# DebugSwitch.net
KiCad netlist of a schematic drawn in Altium Designer
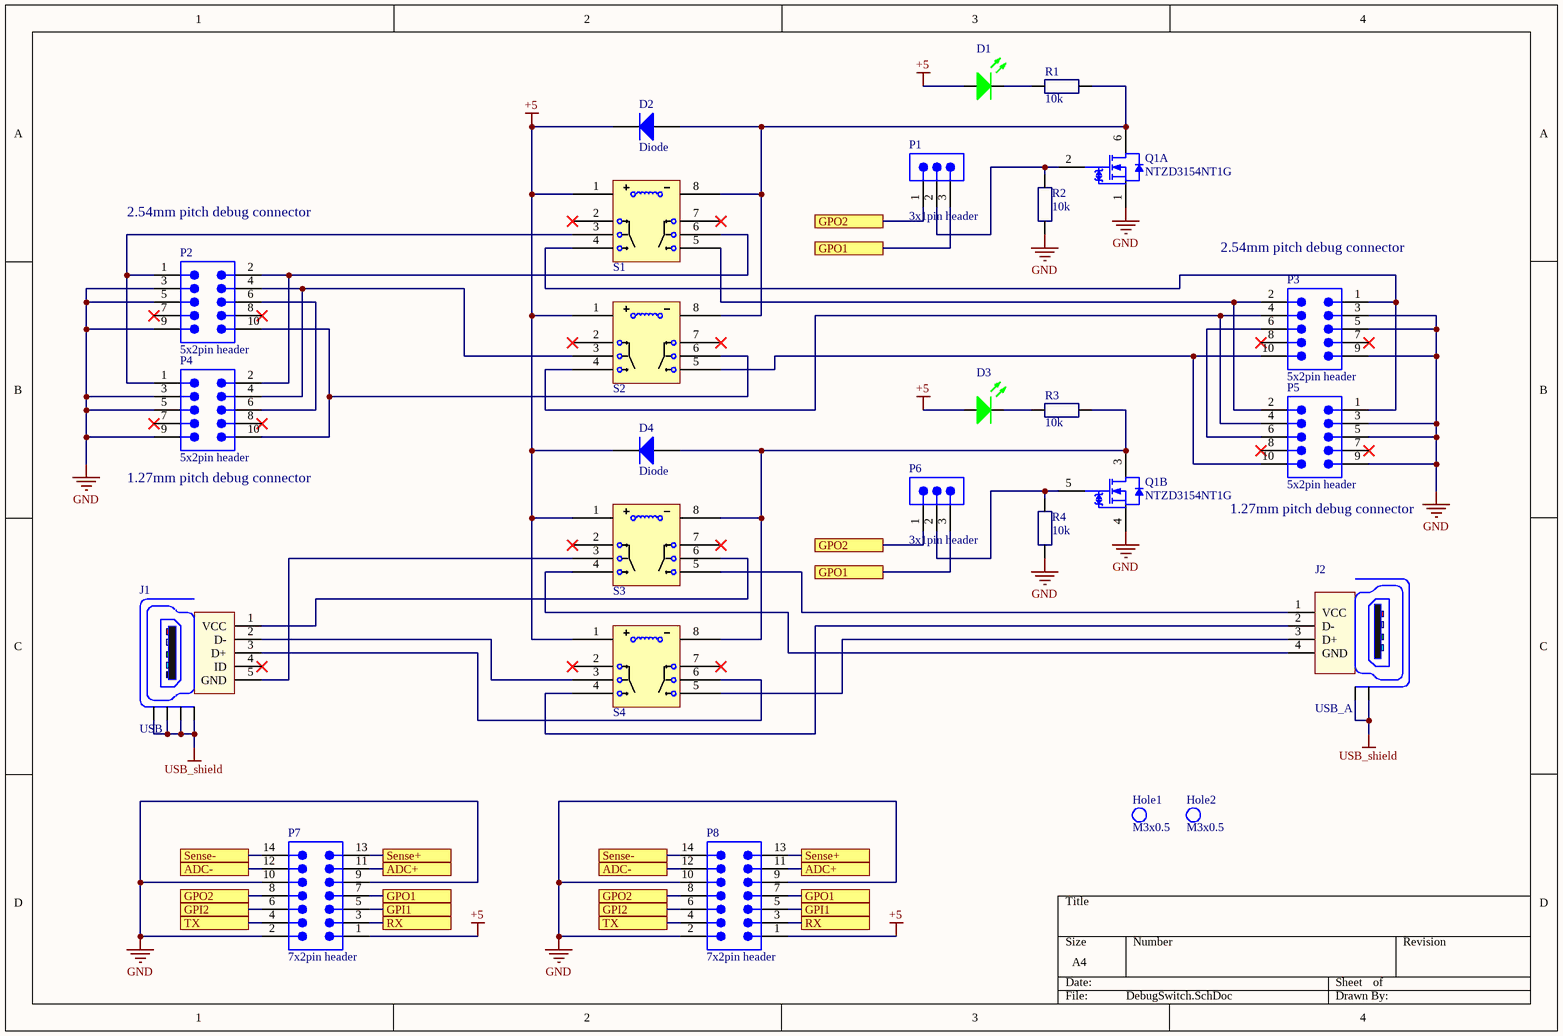
[diagram p0: DebugSwitch.SchDoc]

(export (version "E")
  (design (tool "Eeschema 10.0.6"))
  (components
    (comp (ref "D1")
      (value "LED_GREEN")
      (footprint "LED_0603")
      (libsource (lib "Bjorn_temp") (part "LED_GREEN"))
    )
    (comp (ref "D2")
      (value "Diode")
      (footprint "SOD-123")
      (description "Generic diode")
      (libsource (lib "Bjorn_temp") (part "Diode"))
    )
    (comp (ref "D3")
      (value "LED_GREEN")
      (footprint "LED_0603")
      (libsource (lib "Bjorn_temp") (part "LED_GREEN"))
    )
    (comp (ref "D4")
      (value "Diode")
      (footprint "SOD-123")
      (description "Generic diode")
      (libsource (lib "Bjorn_temp") (part "Diode"))
    )
    (comp (ref "Hole1") (value "M3x0.5") (footprint "M3x0.5") (libsource (lib "Bjorn_temp") (part "M3x0.5")))
    (comp (ref "Hole2") (value "M3x0.5") (footprint "M3x0.5") (libsource (lib "Bjorn_temp") (part "M3x0.5")))
    (comp (ref "J1") (value "USB") (footprint "USB_microB") (libsource (lib "Bjorn_temp") (part "USB")))
    (comp (ref "J2")
      (value "USB_A")
      (footprint "USB-A-S-F-W-SM2")
      (libsource (lib "Bjorn_temp") (part "USB_A"))
    )
    (comp (ref "P1")
      (value "3x1pin header")
      (footprint "TSM-103-01-T-SV")
      (fields (field (name "MANUFACTURER") "Samtec") (field (name "PARTNUMBER") "TSM-103-01-T-SV"))
      (libsource (lib "Bjorn_temp") (part "3x1pin header"))
    )
    (comp (ref "P2")
      (value "5x2pin header")
      (footprint "TSM-105-01-L-DV")
      (fields (field (name "MANUFACTURER") "Samtec") (field (name "PARTNUMBER") "TSM-105-01-L-DV"))
      (libsource (lib "Bjorn_temp") (part "5x2pin header"))
    )
    (comp (ref "P3")
      (value "5x2pin header")
      (footprint "TSM-105-01-L-DV")
      (fields (field (name "MANUFACTURER") "Samtec") (field (name "PARTNUMBER") "TSM-105-01-L-DV"))
      (libsource (lib "Bjorn_temp") (part "5x2pin header"))
    )
    (comp (ref "P4")
      (value "5x2pin header")
      (footprint "FTSH-105-01-F-DV")
      (fields (field (name "MANUFACTURER") "Samtec") (field (name "PARTNUMBER") "TSM-105-01-L-DV"))
      (libsource (lib "Bjorn_temp") (part "5x2pin header"))
    )
    (comp (ref "P5")
      (value "5x2pin header")
      (footprint "FTSH-105-01-F-DV")
      (fields (field (name "MANUFACTURER") "Samtec") (field (name "PARTNUMBER") "TSM-105-01-L-DV"))
      (libsource (lib "Bjorn_temp") (part "5x2pin header"))
    )
    (comp (ref "P6")
      (value "3x1pin header")
      (footprint "TSM-103-01-T-SV")
      (fields (field (name "MANUFACTURER") "Samtec") (field (name "PARTNUMBER") "TSM-103-01-T-SV"))
      (libsource (lib "Bjorn_temp") (part "3x1pin header"))
    )
    (comp (ref "P7")
      (value "7x2pin header")
      (footprint "SSQ-107-02-T-D-RA")
      (fields (field (name "MANUFACTURER") "Samtec") (field (name "PARTNUMBER") "HTSS-107-01-L-DV"))
      (libsource (lib "Bjorn_temp") (part "7x2pin header"))
    )
    (comp (ref "P8")
      (value "7x2pin header")
      (footprint "TSS-107-04-L-D-RA")
      (fields (field (name "MANUFACTURER") "Samtec") (field (name "PARTNUMBER") "HTSS-107-01-L-DV"))
      (libsource (lib "Bjorn_temp") (part "7x2pin header"))
    )
    (comp (ref "Q1")
      (value "NTZD3154NT1G")
      (footprint "SOT-563-6")
      (description "Small Signal MOSFET, 20 V, 540 mA, Dual N-Channel, 6-Pin SOT-563, Pb-Free, Tape and Reel")
      (fields (field (name "MANUFACTURER") "On Semiconductor"))
      (libsource (lib "Bjorn_temp") (part "NTZD3154NT1G"))
    )
    (comp (ref "R1")
      (value "10k")
      (footprint "RES_0402")
      (description "SMD Chip Resistor 0402")
      (fields (field (name "Comment") "RES_0402"))
      (libsource (lib "") (part "RES_0402_1"))
    )
    (comp (ref "R2")
      (value "10k")
      (footprint "RES_0402")
      (description "SMD Chip Resistor 0402")
      (fields (field (name "Comment") "RES_0402"))
      (libsource (lib "Resistors") (part "RES_0402"))
    )
    (comp (ref "R3")
      (value "10k")
      (footprint "RES_0402")
      (description "SMD Chip Resistor 0402")
      (fields (field (name "Comment") "RES_0402"))
      (libsource (lib "") (part "RES_0402_1"))
    )
    (comp (ref "R4")
      (value "10k")
      (footprint "RES_0402")
      (description "SMD Chip Resistor 0402")
      (fields (field (name "Comment") "RES_0402"))
      (libsource (lib "Resistors") (part "RES_0402"))
    )
    (comp (ref "S1")
      (value "Relay_DPDT")
      (footprint "EE2-5NU")
      (description "Relay DPDT")
      (libsource (lib "Bjorn_temp") (part "Relay_DPDT"))
    )
    (comp (ref "S2")
      (value "Relay_DPDT")
      (footprint "EE2-5NU")
      (description "Relay DPDT")
      (libsource (lib "Bjorn_temp") (part "Relay_DPDT"))
    )
    (comp (ref "S3")
      (value "Relay_DPDT")
      (footprint "EE2-5NU")
      (description "Relay DPDT")
      (libsource (lib "Bjorn_temp") (part "Relay_DPDT"))
    )
    (comp (ref "S4")
      (value "Relay_DPDT")
      (footprint "EE2-5NU")
      (description "Relay DPDT")
      (libsource (lib "Bjorn_temp") (part "Relay_DPDT"))
    )
  )
  (nets
    (net (code "1") (name "+5") (class "Default")
      (node (ref "D1") (pin "2") (pinfunction "A_2") (pintype "passive"))
      (node (ref "D2") (pin "1") (pinfunction "K_1") (pintype "passive"))
      (node (ref "D3") (pin "2") (pinfunction "A_2") (pintype "passive"))
      (node (ref "D4") (pin "1") (pinfunction "K_1") (pintype "passive"))
      (node (ref "P7") (pin "1") (pinfunction "1_1") (pintype "passive"))
      (node (ref "P8") (pin "1") (pinfunction "1_1") (pintype "passive"))
      (node (ref "S1") (pin "1") (pintype "passive"))
      (node (ref "S2") (pin "1") (pintype "passive"))
      (node (ref "S3") (pin "1") (pintype "passive"))
      (node (ref "S4") (pin "1") (pintype "passive"))
    )
    (net (code "2") (name "/ADC+") (class "Default")
      (node (ref "P7") (pin "11") (pinfunction "11_11") (pintype "passive"))
      (node (ref "P8") (pin "11") (pinfunction "11_11") (pintype "passive"))
    )
    (net (code "3") (name "/ADC-") (class "Default")
      (node (ref "P7") (pin "12") (pinfunction "12_12") (pintype "passive"))
      (node (ref "P8") (pin "12") (pinfunction "12_12") (pintype "passive"))
    )
    (net (code "4") (name "/GPI1") (class "Default")
      (node (ref "P7") (pin "5") (pinfunction "5_5") (pintype "passive"))
      (node (ref "P8") (pin "5") (pinfunction "5_5") (pintype "passive"))
    )
    (net (code "5") (name "/GPI2") (class "Default")
      (node (ref "P7") (pin "6") (pinfunction "6_6") (pintype "passive"))
      (node (ref "P8") (pin "6") (pinfunction "6_6") (pintype "passive"))
    )
    (net (code "6") (name "/GPO1") (class "Default")
      (node (ref "P1") (pin "3") (pinfunction "3_3") (pintype "passive"))
      (node (ref "P6") (pin "3") (pinfunction "3_3") (pintype "passive"))
      (node (ref "P7") (pin "7") (pinfunction "7_7") (pintype "passive"))
      (node (ref "P8") (pin "7") (pinfunction "7_7") (pintype "passive"))
    )
    (net (code "7") (name "/GPO2") (class "Default")
      (node (ref "P1") (pin "1") (pinfunction "1_1") (pintype "passive"))
      (node (ref "P6") (pin "1") (pinfunction "1_1") (pintype "passive"))
      (node (ref "P7") (pin "8") (pinfunction "8_8") (pintype "passive"))
      (node (ref "P8") (pin "8") (pinfunction "8_8") (pintype "passive"))
    )
    (net (code "8") (name "/RX") (class "Default")
      (node (ref "P7") (pin "3") (pinfunction "3_3") (pintype "passive"))
      (node (ref "P8") (pin "3") (pinfunction "3_3") (pintype "passive"))
    )
    (net (code "9") (name "/Sense+") (class "Default")
      (node (ref "P7") (pin "13") (pinfunction "13_13") (pintype "passive"))
      (node (ref "P8") (pin "13") (pinfunction "13_13") (pintype "passive"))
    )
    (net (code "10") (name "/Sense-") (class "Default")
      (node (ref "P7") (pin "14") (pinfunction "14_14") (pintype "passive"))
      (node (ref "P8") (pin "14") (pinfunction "14_14") (pintype "passive"))
    )
    (net (code "11") (name "/TX") (class "Default")
      (node (ref "P7") (pin "4") (pinfunction "4_4") (pintype "passive"))
      (node (ref "P8") (pin "4") (pinfunction "4_4") (pintype "passive"))
    )
    (net (code "12") (name "GND") (class "Default")
      (node (ref "P2") (pin "3") (pinfunction "3_3") (pintype "passive"))
      (node (ref "P2") (pin "5") (pinfunction "5_5") (pintype "passive"))
      (node (ref "P2") (pin "9") (pinfunction "9_9") (pintype "passive"))
      (node (ref "P3") (pin "3") (pinfunction "3_3") (pintype "passive"))
      (node (ref "P3") (pin "5") (pinfunction "5_5") (pintype "passive"))
      (node (ref "P3") (pin "9") (pinfunction "9_9") (pintype "passive"))
      (node (ref "P4") (pin "3") (pinfunction "3_3") (pintype "passive"))
      (node (ref "P4") (pin "5") (pinfunction "5_5") (pintype "passive"))
      (node (ref "P4") (pin "9") (pinfunction "9_9") (pintype "passive"))
      (node (ref "P5") (pin "3") (pinfunction "3_3") (pintype "passive"))
      (node (ref "P5") (pin "5") (pinfunction "5_5") (pintype "passive"))
      (node (ref "P5") (pin "9") (pinfunction "9_9") (pintype "passive"))
      (node (ref "P7") (pin "10") (pinfunction "10_10") (pintype "passive"))
      (node (ref "P7") (pin "2") (pinfunction "2_2") (pintype "passive"))
      (node (ref "P7") (pin "9") (pinfunction "9_9") (pintype "passive"))
      (node (ref "P8") (pin "10") (pinfunction "10_10") (pintype "passive"))
      (node (ref "P8") (pin "2") (pinfunction "2_2") (pintype "passive"))
      (node (ref "P8") (pin "9") (pinfunction "9_9") (pintype "passive"))
      (node (ref "Q1") (pin "1") (pinfunction "S1_1") (pintype "passive"))
      (node (ref "Q1") (pin "4") (pinfunction "S2_4") (pintype "passive"))
      (node (ref "R2") (pin "1") (pinfunction "1_1") (pintype "passive"))
      (node (ref "R4") (pin "1") (pinfunction "1_1") (pintype "passive"))
    )
    (net (code "13") (name "Net-(D1-K)") (class "Default")
      (node (ref "D1") (pin "1") (pinfunction "K_1") (pintype "passive"))
      (node (ref "R1") (pin "1") (pinfunction "1_1") (pintype "passive"))
    )
    (net (code "14") (name "Net-(D2-A)") (class "Default")
      (node (ref "D2") (pin "2") (pinfunction "A_2") (pintype "passive"))
      (node (ref "Q1") (pin "6") (pinfunction "D1_6") (pintype "passive"))
      (node (ref "R1") (pin "2") (pinfunction "2_2") (pintype "passive"))
      (node (ref "S1") (pin "8") (pintype "passive"))
      (node (ref "S2") (pin "8") (pintype "passive"))
    )
    (net (code "15") (name "Net-(D3-K)") (class "Default")
      (node (ref "D3") (pin "1") (pinfunction "K_1") (pintype "passive"))
      (node (ref "R3") (pin "1") (pinfunction "1_1") (pintype "passive"))
    )
    (net (code "16") (name "Net-(D4-A)") (class "Default")
      (node (ref "D4") (pin "2") (pinfunction "A_2") (pintype "passive"))
      (node (ref "Q1") (pin "3") (pinfunction "D2_3") (pintype "passive"))
      (node (ref "R3") (pin "2") (pinfunction "2_2") (pintype "passive"))
      (node (ref "S3") (pin "8") (pintype "passive"))
      (node (ref "S4") (pin "8") (pintype "passive"))
    )
    (net (code "17") (name "Net-(J1-D+)") (class "Default")
      (node (ref "J1") (pin "3") (pinfunction "D+_3") (pintype "passive"))
      (node (ref "S4") (pin "6") (pintype "passive"))
    )
    (net (code "18") (name "Net-(J1-D-)") (class "Default")
      (node (ref "J1") (pin "2") (pinfunction "D-_2") (pintype "passive"))
      (node (ref "S4") (pin "3") (pintype "passive"))
    )
    (net (code "19") (name "Net-(J1-GND)") (class "Default")
      (node (ref "J1") (pin "5") (pinfunction "GND_5") (pintype "passive"))
      (node (ref "S3") (pin "3") (pintype "passive"))
    )
    (net (code "20") (name "Net-(J1-VCC)") (class "Default")
      (node (ref "J1") (pin "1") (pinfunction "VCC_1") (pintype "passive"))
      (node (ref "S3") (pin "6") (pintype "passive"))
    )
    (net (code "21") (name "Net-(J2-D+)") (class "Default")
      (node (ref "J2") (pin "3") (pinfunction "D+_3") (pintype "passive"))
      (node (ref "S4") (pin "5") (pintype "passive"))
    )
    (net (code "22") (name "Net-(J2-D-)") (class "Default")
      (node (ref "J2") (pin "2") (pinfunction "D-_2") (pintype "passive"))
      (node (ref "S4") (pin "4") (pintype "passive"))
    )
    (net (code "23") (name "Net-(J2-GND)") (class "Default")
      (node (ref "J2") (pin "4") (pinfunction "GND_4") (pintype "passive"))
      (node (ref "S3") (pin "4") (pintype "passive"))
    )
    (net (code "24") (name "Net-(J2-VCC)") (class "Default")
      (node (ref "J2") (pin "1") (pinfunction "VCC_1") (pintype "passive"))
      (node (ref "S3") (pin "5") (pintype "passive"))
    )
    (net (code "25") (name "Net-(P2-Pad1)") (class "Default")
      (node (ref "P2") (pin "1") (pinfunction "1_1") (pintype "passive"))
      (node (ref "P4") (pin "1") (pinfunction "1_1") (pintype "passive"))
      (node (ref "S1") (pin "3") (pintype "passive"))
    )
    (net (code "26") (name "Net-(P2-Pad2)") (class "Default")
      (node (ref "P2") (pin "2") (pinfunction "2_2") (pintype "passive"))
      (node (ref "P4") (pin "2") (pinfunction "2_2") (pintype "passive"))
      (node (ref "S1") (pin "6") (pintype "passive"))
    )
    (net (code "27") (name "Net-(P2-Pad4)") (class "Default")
      (node (ref "P2") (pin "4") (pinfunction "4_4") (pintype "passive"))
      (node (ref "P4") (pin "4") (pinfunction "4_4") (pintype "passive"))
      (node (ref "S2") (pin "3") (pintype "passive"))
    )
    (net (code "28") (name "Net-(P2-Pad6)") (class "Default")
      (node (ref "P2") (pin "6") (pinfunction "6_6") (pintype "passive"))
      (node (ref "P4") (pin "6") (pinfunction "6_6") (pintype "passive"))
    )
    (net (code "29") (name "Net-(P2-Pad10)") (class "Default")
      (node (ref "P2") (pin "10") (pinfunction "10_10") (pintype "passive"))
      (node (ref "P4") (pin "10") (pinfunction "10_10") (pintype "passive"))
      (node (ref "S2") (pin "6") (pintype "passive"))
    )
    (net (code "30") (name "Net-(P3-Pad1)") (class "Default")
      (node (ref "P3") (pin "1") (pinfunction "1_1") (pintype "passive"))
      (node (ref "P5") (pin "1") (pinfunction "1_1") (pintype "passive"))
      (node (ref "S1") (pin "4") (pintype "passive"))
    )
    (net (code "31") (name "Net-(P3-Pad2)") (class "Default")
      (node (ref "P3") (pin "2") (pinfunction "2_2") (pintype "passive"))
      (node (ref "P5") (pin "2") (pinfunction "2_2") (pintype "passive"))
      (node (ref "S1") (pin "5") (pintype "passive"))
    )
    (net (code "32") (name "Net-(P3-Pad4)") (class "Default")
      (node (ref "P3") (pin "4") (pinfunction "4_4") (pintype "passive"))
      (node (ref "P5") (pin "4") (pinfunction "4_4") (pintype "passive"))
      (node (ref "S2") (pin "4") (pintype "passive"))
    )
    (net (code "33") (name "Net-(P3-Pad6)") (class "Default")
      (node (ref "P3") (pin "6") (pinfunction "6_6") (pintype "passive"))
      (node (ref "P5") (pin "6") (pinfunction "6_6") (pintype "passive"))
    )
    (net (code "34") (name "Net-(P3-Pad10)") (class "Default")
      (node (ref "P3") (pin "10") (pinfunction "10_10") (pintype "passive"))
      (node (ref "P5") (pin "10") (pinfunction "10_10") (pintype "passive"))
      (node (ref "S2") (pin "5") (pintype "passive"))
    )
    (net (code "35") (name "Net-(Q1A-G1)") (class "Default")
      (node (ref "P1") (pin "2") (pinfunction "2_2") (pintype "passive"))
      (node (ref "Q1") (pin "2") (pinfunction "G1_2") (pintype "passive"))
      (node (ref "R2") (pin "2") (pinfunction "2_2") (pintype "passive"))
    )
    (net (code "36") (name "Net-(Q1B-G2)") (class "Default")
      (node (ref "P6") (pin "2") (pinfunction "2_2") (pintype "passive"))
      (node (ref "Q1") (pin "5") (pinfunction "G2_5") (pintype "passive"))
      (node (ref "R4") (pin "2") (pinfunction "2_2") (pintype "passive"))
    )
    (net (code "37") (name "USB_shield") (class "Default")
      (node (ref "J1") (pin "Z1") (pinfunction "Shield_Z1") (pintype "passive"))
      (node (ref "J1") (pin "Z2") (pinfunction "Shield_Z2") (pintype "passive"))
      (node (ref "J1") (pin "Z3") (pinfunction "Shield_Z3") (pintype "passive"))
      (node (ref "J1") (pin "Z4") (pinfunction "Shield_Z4") (pintype "passive"))
      (node (ref "J2") (pin "Z1") (pinfunction "Shield_Z1") (pintype "passive"))
      (node (ref "J2") (pin "Z2") (pinfunction "Shield_Z2") (pintype "passive"))
    )
    (net (code "38") (name "unconnected-(J1-ID-Pad4)") (class "Default")
      (node (ref "J1") (pin "4") (pinfunction "ID_4") (pintype "passive+no_connect"))
    )
    (net (code "39") (name "unconnected-(P2-Pad7)") (class "Default")
      (node (ref "P2") (pin "7") (pinfunction "7_7") (pintype "passive+no_connect"))
    )
    (net (code "40") (name "unconnected-(P2-Pad8)") (class "Default")
      (node (ref "P2") (pin "8") (pinfunction "8_8") (pintype "passive+no_connect"))
    )
    (net (code "41") (name "unconnected-(P3-Pad7)") (class "Default")
      (node (ref "P3") (pin "7") (pinfunction "7_7") (pintype "passive+no_connect"))
    )
    (net (code "42") (name "unconnected-(P3-Pad8)") (class "Default")
      (node (ref "P3") (pin "8") (pinfunction "8_8") (pintype "passive+no_connect"))
    )
    (net (code "43") (name "unconnected-(P4-Pad7)") (class "Default")
      (node (ref "P4") (pin "7") (pinfunction "7_7") (pintype "passive+no_connect"))
    )
    (net (code "44") (name "unconnected-(P4-Pad8)") (class "Default")
      (node (ref "P4") (pin "8") (pinfunction "8_8") (pintype "passive+no_connect"))
    )
    (net (code "45") (name "unconnected-(P5-Pad7)") (class "Default")
      (node (ref "P5") (pin "7") (pinfunction "7_7") (pintype "passive+no_connect"))
    )
    (net (code "46") (name "unconnected-(P5-Pad8)") (class "Default")
      (node (ref "P5") (pin "8") (pinfunction "8_8") (pintype "passive+no_connect"))
    )
    (net (code "47") (name "unconnected-(S1-Pad2)") (class "Default")
      (node (ref "S1") (pin "2") (pintype "passive+no_connect"))
    )
    (net (code "48") (name "unconnected-(S1-Pad7)") (class "Default")
      (node (ref "S1") (pin "7") (pintype "passive+no_connect"))
    )
    (net (code "49") (name "unconnected-(S2-Pad2)") (class "Default")
      (node (ref "S2") (pin "2") (pintype "passive+no_connect"))
    )
    (net (code "50") (name "unconnected-(S2-Pad7)") (class "Default")
      (node (ref "S2") (pin "7") (pintype "passive+no_connect"))
    )
    (net (code "51") (name "unconnected-(S3-Pad2)") (class "Default")
      (node (ref "S3") (pin "2") (pintype "passive+no_connect"))
    )
    (net (code "52") (name "unconnected-(S3-Pad7)") (class "Default")
      (node (ref "S3") (pin "7") (pintype "passive+no_connect"))
    )
    (net (code "53") (name "unconnected-(S4-Pad2)") (class "Default")
      (node (ref "S4") (pin "2") (pintype "passive+no_connect"))
    )
    (net (code "54") (name "unconnected-(S4-Pad7)") (class "Default")
      (node (ref "S4") (pin "7") (pintype "passive+no_connect"))
    )
  )
)
